# tinyg_g2_breakout_v1.net
KiCad netlist of a schematic drawn in EAGLE
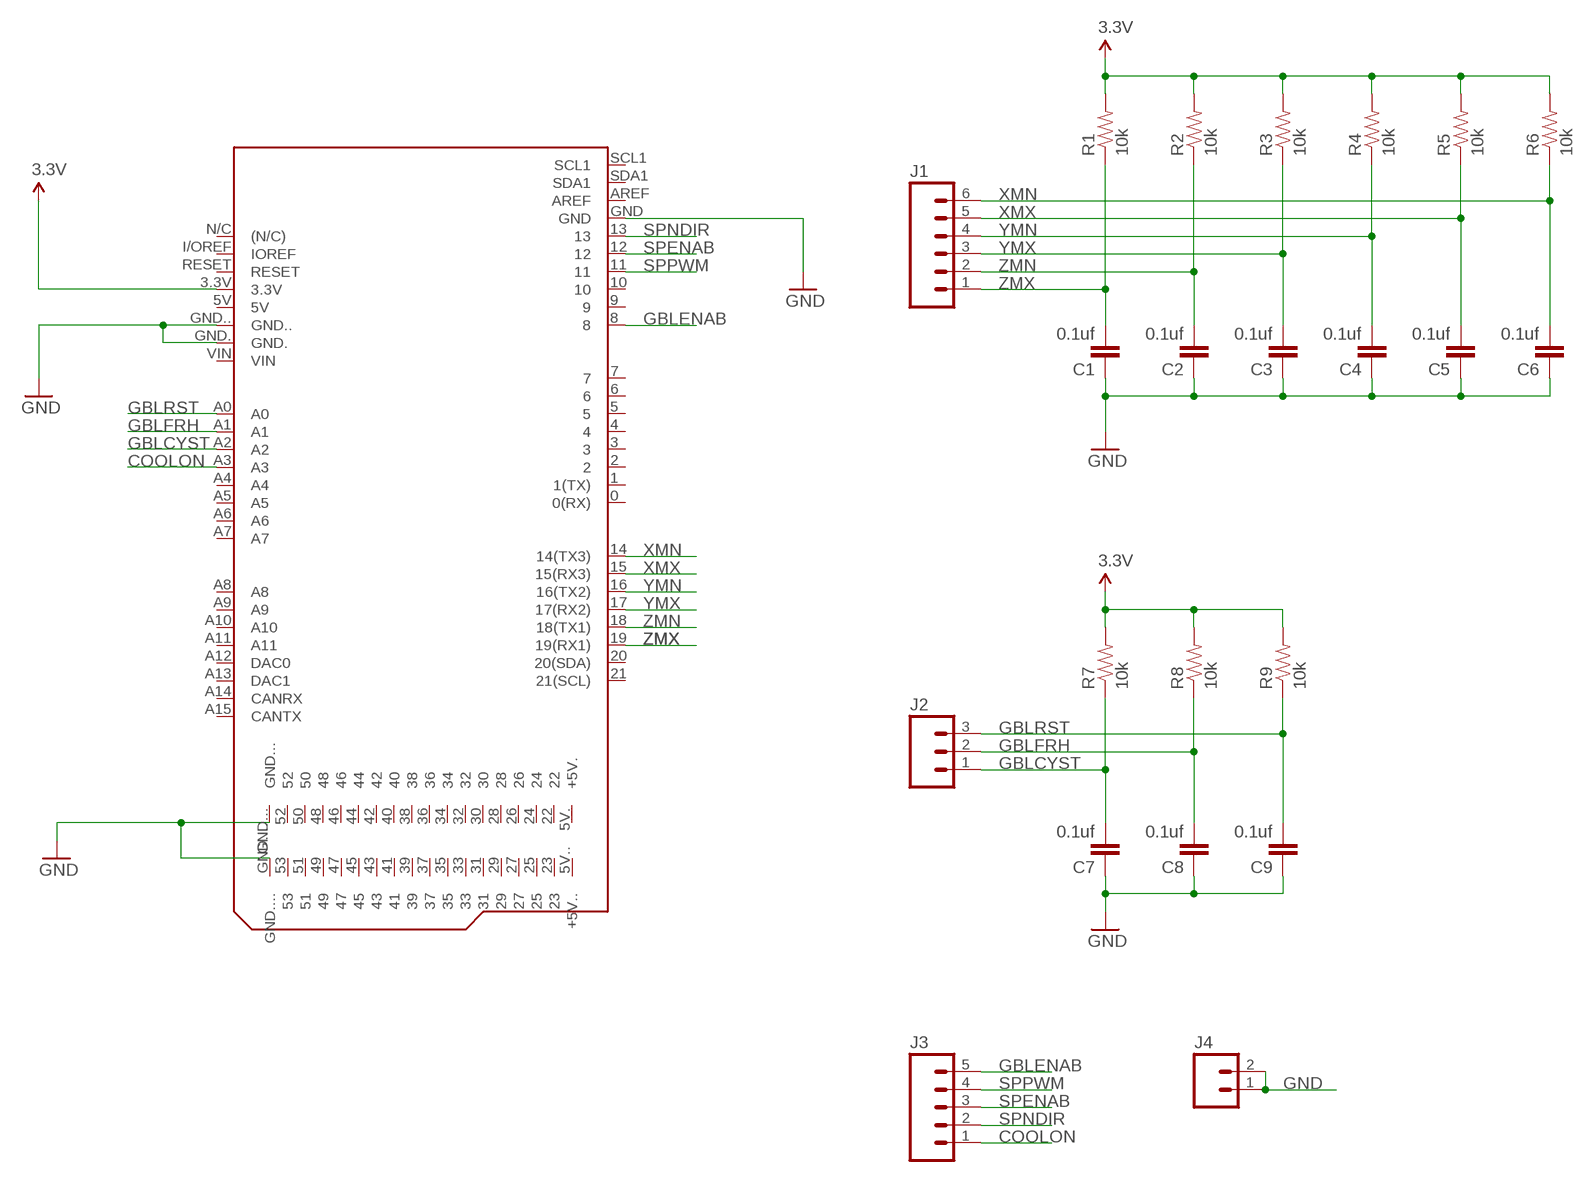
[diagram p0: schematic, sheet 1]

(export (version "E")
  (design (tool "Eeschema 10.0.6"))
  (components
    (comp (ref "C1")
      (value "0.1uf")
      (footprint "eagle-import:CAP-PTH-SMALL")
      (libsource (lib "eagle-import") (part "CAPPTH"))
    )
    (comp (ref "C2")
      (value "0.1uf")
      (footprint "eagle-import:CAP-PTH-SMALL")
      (libsource (lib "eagle-import") (part "CAPPTH"))
    )
    (comp (ref "C3")
      (value "0.1uf")
      (footprint "eagle-import:CAP-PTH-SMALL")
      (libsource (lib "eagle-import") (part "CAPPTH"))
    )
    (comp (ref "C4")
      (value "0.1uf")
      (footprint "eagle-import:CAP-PTH-SMALL")
      (libsource (lib "eagle-import") (part "CAPPTH"))
    )
    (comp (ref "C5")
      (value "0.1uf")
      (footprint "eagle-import:CAP-PTH-SMALL")
      (libsource (lib "eagle-import") (part "CAPPTH"))
    )
    (comp (ref "C6")
      (value "0.1uf")
      (footprint "eagle-import:CAP-PTH-SMALL")
      (libsource (lib "eagle-import") (part "CAPPTH"))
    )
    (comp (ref "C7")
      (value "0.1uf")
      (footprint "eagle-import:CAP-PTH-SMALL")
      (libsource (lib "eagle-import") (part "CAPPTH"))
    )
    (comp (ref "C8")
      (value "0.1uf")
      (footprint "eagle-import:CAP-PTH-SMALL")
      (libsource (lib "eagle-import") (part "CAPPTH"))
    )
    (comp (ref "C9")
      (value "0.1uf")
      (footprint "eagle-import:CAP-PTH-SMALL")
      (libsource (lib "eagle-import") (part "CAPPTH"))
    )
    (comp (ref "J1")
      (value "M06SILK_FEMALE_PTH")
      (footprint "eagle-import:1X06")
      (libsource (lib "eagle-import") (part "M06SILK_FEMALE_PTH"))
    )
    (comp (ref "J2")
      (value "M03PTH")
      (footprint "eagle-import:1X03")
      (libsource (lib "eagle-import") (part "M03PTH"))
    )
    (comp (ref "J3")
      (value "M05PTH")
      (footprint "eagle-import:1X05")
      (libsource (lib "eagle-import") (part "M05PTH"))
    )
    (comp (ref "J4")
      (value "M02PTH")
      (footprint "eagle-import:1X02")
      (libsource (lib "eagle-import") (part "M02PTH"))
    )
    (comp (ref "PCB1")
      (value "ARDUINO_DUE_SHIELD")
      (footprint "eagle-import:ARDUINO_DUE_SHIELD")
      (libsource (lib "eagle-import") (part "ARDUINO_DUE_SHIELD"))
    )
    (comp (ref "R1")
      (value "10k")
      (footprint "eagle-import:AXIAL-0.3")
      (libsource (lib "eagle-import") (part "RESISTORAXIAL-0.3"))
    )
    (comp (ref "R2")
      (value "10k")
      (footprint "eagle-import:AXIAL-0.3")
      (libsource (lib "eagle-import") (part "RESISTORAXIAL-0.3"))
    )
    (comp (ref "R3")
      (value "10k")
      (footprint "eagle-import:AXIAL-0.3")
      (libsource (lib "eagle-import") (part "RESISTORAXIAL-0.3"))
    )
    (comp (ref "R4")
      (value "10k")
      (footprint "eagle-import:AXIAL-0.3")
      (libsource (lib "eagle-import") (part "RESISTORAXIAL-0.3"))
    )
    (comp (ref "R5")
      (value "10k")
      (footprint "eagle-import:AXIAL-0.3")
      (libsource (lib "eagle-import") (part "RESISTORAXIAL-0.3"))
    )
    (comp (ref "R6")
      (value "10k")
      (footprint "eagle-import:AXIAL-0.3")
      (libsource (lib "eagle-import") (part "RESISTORAXIAL-0.3"))
    )
    (comp (ref "R7")
      (value "10k")
      (footprint "eagle-import:AXIAL-0.3")
      (libsource (lib "eagle-import") (part "RESISTORAXIAL-0.3"))
    )
    (comp (ref "R8")
      (value "10k")
      (footprint "eagle-import:AXIAL-0.3")
      (libsource (lib "eagle-import") (part "RESISTORAXIAL-0.3"))
    )
    (comp (ref "R9")
      (value "10k")
      (footprint "eagle-import:AXIAL-0.3")
      (libsource (lib "eagle-import") (part "RESISTORAXIAL-0.3"))
    )
  )
  (nets
    (net (code "1") (name "/COOLON") (class "Default")
      (node (ref "J3") (pin "1") (pinfunction "1_1") (pintype "passive"))
      (node (ref "PCB1") (pin "A3") (pinfunction "A3_A3") (pintype "bidirectional"))
    )
    (net (code "2") (name "/GBLCYST") (class "Default")
      (node (ref "C7") (pin "2") (pinfunction "2_2") (pintype "passive"))
      (node (ref "J2") (pin "1") (pinfunction "1_1") (pintype "passive"))
      (node (ref "PCB1") (pin "A2") (pinfunction "A2_A2") (pintype "bidirectional"))
      (node (ref "R7") (pin "P$1") (pinfunction "1_P$1") (pintype "passive"))
    )
    (net (code "3") (name "/GBLENAB") (class "Default")
      (node (ref "J3") (pin "5") (pinfunction "5_5") (pintype "passive"))
      (node (ref "PCB1") (pin "8") (pinfunction "8_8") (pintype "bidirectional"))
    )
    (net (code "4") (name "/GBLFRH") (class "Default")
      (node (ref "C8") (pin "2") (pinfunction "2_2") (pintype "passive"))
      (node (ref "J2") (pin "2") (pinfunction "2_2") (pintype "passive"))
      (node (ref "PCB1") (pin "A1") (pinfunction "A1_A1") (pintype "bidirectional"))
      (node (ref "R8") (pin "P$1") (pinfunction "1_P$1") (pintype "passive"))
    )
    (net (code "5") (name "/GBLRST") (class "Default")
      (node (ref "C9") (pin "2") (pinfunction "2_2") (pintype "passive"))
      (node (ref "J2") (pin "3") (pinfunction "3_3") (pintype "passive"))
      (node (ref "PCB1") (pin "A0") (pinfunction "A0_A0") (pintype "bidirectional"))
      (node (ref "R9") (pin "P$1") (pinfunction "1_P$1") (pintype "passive"))
    )
    (net (code "6") (name "/SPENAB") (class "Default")
      (node (ref "J3") (pin "3") (pinfunction "3_3") (pintype "passive"))
      (node (ref "PCB1") (pin "12") (pinfunction "12_12") (pintype "bidirectional"))
    )
    (net (code "7") (name "/SPNDIR") (class "Default")
      (node (ref "J3") (pin "2") (pinfunction "2_2") (pintype "passive"))
      (node (ref "PCB1") (pin "13") (pinfunction "13_13") (pintype "bidirectional"))
    )
    (net (code "8") (name "/SPPWM") (class "Default")
      (node (ref "J3") (pin "4") (pinfunction "4_4") (pintype "passive"))
      (node (ref "PCB1") (pin "11") (pinfunction "11_11") (pintype "bidirectional"))
    )
    (net (code "9") (name "/XMN") (class "Default")
      (node (ref "C6") (pin "2") (pinfunction "2_2") (pintype "passive"))
      (node (ref "J1") (pin "6") (pinfunction "6_6") (pintype "passive"))
      (node (ref "PCB1") (pin "14") (pinfunction "14(TX3)_14") (pintype "bidirectional"))
      (node (ref "R6") (pin "P$1") (pinfunction "1_P$1") (pintype "passive"))
    )
    (net (code "10") (name "/XMX") (class "Default")
      (node (ref "C5") (pin "2") (pinfunction "2_2") (pintype "passive"))
      (node (ref "J1") (pin "5") (pinfunction "5_5") (pintype "passive"))
      (node (ref "PCB1") (pin "15") (pinfunction "15(RX3)_15") (pintype "bidirectional"))
      (node (ref "R5") (pin "P$1") (pinfunction "1_P$1") (pintype "passive"))
    )
    (net (code "11") (name "/YMN") (class "Default")
      (node (ref "C4") (pin "2") (pinfunction "2_2") (pintype "passive"))
      (node (ref "J1") (pin "4") (pinfunction "4_4") (pintype "passive"))
      (node (ref "PCB1") (pin "16") (pinfunction "16(TX2)_16") (pintype "bidirectional"))
      (node (ref "R4") (pin "P$1") (pinfunction "1_P$1") (pintype "passive"))
    )
    (net (code "12") (name "/YMX") (class "Default")
      (node (ref "C3") (pin "2") (pinfunction "2_2") (pintype "passive"))
      (node (ref "J1") (pin "3") (pinfunction "3_3") (pintype "passive"))
      (node (ref "PCB1") (pin "17") (pinfunction "17(RX2)_17") (pintype "bidirectional"))
      (node (ref "R3") (pin "P$1") (pinfunction "1_P$1") (pintype "passive"))
    )
    (net (code "13") (name "/ZMN") (class "Default")
      (node (ref "C2") (pin "2") (pinfunction "2_2") (pintype "passive"))
      (node (ref "J1") (pin "2") (pinfunction "2_2") (pintype "passive"))
      (node (ref "PCB1") (pin "18") (pinfunction "18(TX1)_18") (pintype "bidirectional"))
      (node (ref "R2") (pin "P$1") (pinfunction "1_P$1") (pintype "passive"))
    )
    (net (code "14") (name "/ZMX") (class "Default")
      (node (ref "C1") (pin "2") (pinfunction "2_2") (pintype "passive"))
      (node (ref "J1") (pin "1") (pinfunction "1_1") (pintype "passive"))
      (node (ref "PCB1") (pin "19") (pinfunction "19(RX1)_19") (pintype "bidirectional"))
      (node (ref "R1") (pin "P$1") (pinfunction "1_P$1") (pintype "passive"))
    )
    (net (code "15") (name "3.3V") (class "Default")
      (node (ref "PCB1") (pin "3.3V") (pinfunction "3.3V_3.3V") (pintype "bidirectional"))
      (node (ref "R1") (pin "P$2") (pinfunction "2_P$2") (pintype "passive"))
      (node (ref "R2") (pin "P$2") (pinfunction "2_P$2") (pintype "passive"))
      (node (ref "R3") (pin "P$2") (pinfunction "2_P$2") (pintype "passive"))
      (node (ref "R4") (pin "P$2") (pinfunction "2_P$2") (pintype "passive"))
      (node (ref "R5") (pin "P$2") (pinfunction "2_P$2") (pintype "passive"))
      (node (ref "R6") (pin "P$2") (pinfunction "2_P$2") (pintype "passive"))
      (node (ref "R7") (pin "P$2") (pinfunction "2_P$2") (pintype "passive"))
      (node (ref "R8") (pin "P$2") (pinfunction "2_P$2") (pintype "passive"))
      (node (ref "R9") (pin "P$2") (pinfunction "2_P$2") (pintype "passive"))
    )
    (net (code "16") (name "GND") (class "Default")
      (node (ref "C1") (pin "1") (pinfunction "1_1") (pintype "passive"))
      (node (ref "C2") (pin "1") (pinfunction "1_1") (pintype "passive"))
      (node (ref "C3") (pin "1") (pinfunction "1_1") (pintype "passive"))
      (node (ref "C4") (pin "1") (pinfunction "1_1") (pintype "passive"))
      (node (ref "C5") (pin "1") (pinfunction "1_1") (pintype "passive"))
      (node (ref "C6") (pin "1") (pinfunction "1_1") (pintype "passive"))
      (node (ref "C7") (pin "1") (pinfunction "1_1") (pintype "passive"))
      (node (ref "C8") (pin "1") (pinfunction "1_1") (pintype "passive"))
      (node (ref "C9") (pin "1") (pinfunction "1_1") (pintype "passive"))
      (node (ref "J4") (pin "1") (pinfunction "1_1") (pintype "passive"))
      (node (ref "J4") (pin "2") (pinfunction "2_2") (pintype "passive"))
      (node (ref "PCB1") (pin "GND") (pinfunction "GND_GND") (pintype "bidirectional"))
      (node (ref "PCB1") (pin "GND.") (pinfunction "GND._GND.") (pintype "bidirectional"))
      (node (ref "PCB1") (pin "GND..") (pinfunction "GND.._GND..") (pintype "bidirectional"))
      (node (ref "PCB1") (pin "GND...") (pinfunction "GND..._GND...") (pintype "bidirectional"))
      (node (ref "PCB1") (pin "GND....") (pinfunction "GND...._GND....") (pintype "bidirectional"))
    )
    (net (code "17") (name "unconnected-(PCB1-(N{slash}C)-PadN{slash}C)") (class "Default")
      (node (ref "PCB1") (pin "N/C") (pinfunction "(N/C)_N/C") (pintype "bidirectional"))
    )
    (net (code "18") (name "unconnected-(PCB1-+5V.-Pad5V.)") (class "Default")
      (node (ref "PCB1") (pin "5V.") (pinfunction "+5V._5V.") (pintype "bidirectional"))
    )
    (net (code "19") (name "unconnected-(PCB1-+5V..-Pad5V..)") (class "Default")
      (node (ref "PCB1") (pin "5V..") (pinfunction "+5V.._5V..") (pintype "bidirectional"))
    )
    (net (code "20") (name "unconnected-(PCB1-0(RX)-Pad0)") (class "Default")
      (node (ref "PCB1") (pin "0") (pinfunction "0(RX)_0") (pintype "bidirectional"))
    )
    (net (code "21") (name "unconnected-(PCB1-1(TX)-Pad1)") (class "Default")
      (node (ref "PCB1") (pin "1") (pinfunction "1(TX)_1") (pintype "bidirectional"))
    )
    (net (code "22") (name "unconnected-(PCB1-20(SDA)-Pad20)") (class "Default")
      (node (ref "PCB1") (pin "20") (pinfunction "20(SDA)_20") (pintype "bidirectional"))
    )
    (net (code "23") (name "unconnected-(PCB1-21(SCL)-Pad21)") (class "Default")
      (node (ref "PCB1") (pin "21") (pinfunction "21(SCL)_21") (pintype "bidirectional"))
    )
    (net (code "24") (name "unconnected-(PCB1-CANRX-PadA14)") (class "Default")
      (node (ref "PCB1") (pin "A14") (pinfunction "CANRX_A14") (pintype "bidirectional"))
    )
    (net (code "25") (name "unconnected-(PCB1-CANTX-PadA15)") (class "Default")
      (node (ref "PCB1") (pin "A15") (pinfunction "CANTX_A15") (pintype "bidirectional"))
    )
    (net (code "26") (name "unconnected-(PCB1-DAC0-PadA12)") (class "Default")
      (node (ref "PCB1") (pin "A12") (pinfunction "DAC0_A12") (pintype "bidirectional"))
    )
    (net (code "27") (name "unconnected-(PCB1-DAC1-PadA13)") (class "Default")
      (node (ref "PCB1") (pin "A13") (pinfunction "DAC1_A13") (pintype "bidirectional"))
    )
    (net (code "28") (name "unconnected-(PCB1-IOREF-PadI{slash}OREF)") (class "Default")
      (node (ref "PCB1") (pin "I/OREF") (pinfunction "IOREF_I/OREF") (pintype "bidirectional"))
    )
    (net (code "29") (name "unconnected-(PCB1-Pad2)") (class "Default")
      (node (ref "PCB1") (pin "2") (pinfunction "2_2") (pintype "bidirectional"))
    )
    (net (code "30") (name "unconnected-(PCB1-Pad3)") (class "Default")
      (node (ref "PCB1") (pin "3") (pinfunction "3_3") (pintype "bidirectional"))
    )
    (net (code "31") (name "unconnected-(PCB1-Pad4)") (class "Default")
      (node (ref "PCB1") (pin "4") (pinfunction "4_4") (pintype "bidirectional"))
    )
    (net (code "32") (name "unconnected-(PCB1-Pad5)") (class "Default")
      (node (ref "PCB1") (pin "5") (pinfunction "5_5") (pintype "bidirectional"))
    )
    (net (code "33") (name "unconnected-(PCB1-Pad5V)") (class "Default")
      (node (ref "PCB1") (pin "5V") (pinfunction "5V_5V") (pintype "bidirectional"))
    )
    (net (code "34") (name "unconnected-(PCB1-Pad6)") (class "Default")
      (node (ref "PCB1") (pin "6") (pinfunction "6_6") (pintype "bidirectional"))
    )
    (net (code "35") (name "unconnected-(PCB1-Pad7)") (class "Default")
      (node (ref "PCB1") (pin "7") (pinfunction "7_7") (pintype "bidirectional"))
    )
    (net (code "36") (name "unconnected-(PCB1-Pad9)") (class "Default")
      (node (ref "PCB1") (pin "9") (pinfunction "9_9") (pintype "bidirectional"))
    )
    (net (code "37") (name "unconnected-(PCB1-Pad10)") (class "Default")
      (node (ref "PCB1") (pin "10") (pinfunction "10_10") (pintype "bidirectional"))
    )
    (net (code "38") (name "unconnected-(PCB1-Pad22)") (class "Default")
      (node (ref "PCB1") (pin "22") (pinfunction "22_22") (pintype "bidirectional"))
    )
    (net (code "39") (name "unconnected-(PCB1-Pad23)") (class "Default")
      (node (ref "PCB1") (pin "23") (pinfunction "23_23") (pintype "bidirectional"))
    )
    (net (code "40") (name "unconnected-(PCB1-Pad24)") (class "Default")
      (node (ref "PCB1") (pin "24") (pinfunction "24_24") (pintype "bidirectional"))
    )
    (net (code "41") (name "unconnected-(PCB1-Pad25)") (class "Default")
      (node (ref "PCB1") (pin "25") (pinfunction "25_25") (pintype "bidirectional"))
    )
    (net (code "42") (name "unconnected-(PCB1-Pad26)") (class "Default")
      (node (ref "PCB1") (pin "26") (pinfunction "26_26") (pintype "bidirectional"))
    )
    (net (code "43") (name "unconnected-(PCB1-Pad27)") (class "Default")
      (node (ref "PCB1") (pin "27") (pinfunction "27_27") (pintype "bidirectional"))
    )
    (net (code "44") (name "unconnected-(PCB1-Pad28)") (class "Default")
      (node (ref "PCB1") (pin "28") (pinfunction "28_28") (pintype "bidirectional"))
    )
    (net (code "45") (name "unconnected-(PCB1-Pad29)") (class "Default")
      (node (ref "PCB1") (pin "29") (pinfunction "29_29") (pintype "bidirectional"))
    )
    (net (code "46") (name "unconnected-(PCB1-Pad30)") (class "Default")
      (node (ref "PCB1") (pin "30") (pinfunction "30_30") (pintype "bidirectional"))
    )
    (net (code "47") (name "unconnected-(PCB1-Pad31)") (class "Default")
      (node (ref "PCB1") (pin "31") (pinfunction "31_31") (pintype "bidirectional"))
    )
    (net (code "48") (name "unconnected-(PCB1-Pad32)") (class "Default")
      (node (ref "PCB1") (pin "32") (pinfunction "32_32") (pintype "bidirectional"))
    )
    (net (code "49") (name "unconnected-(PCB1-Pad33)") (class "Default")
      (node (ref "PCB1") (pin "33") (pinfunction "33_33") (pintype "bidirectional"))
    )
    (net (code "50") (name "unconnected-(PCB1-Pad34)") (class "Default")
      (node (ref "PCB1") (pin "34") (pinfunction "34_34") (pintype "bidirectional"))
    )
    (net (code "51") (name "unconnected-(PCB1-Pad35)") (class "Default")
      (node (ref "PCB1") (pin "35") (pinfunction "35_35") (pintype "bidirectional"))
    )
    (net (code "52") (name "unconnected-(PCB1-Pad36)") (class "Default")
      (node (ref "PCB1") (pin "36") (pinfunction "36_36") (pintype "bidirectional"))
    )
    (net (code "53") (name "unconnected-(PCB1-Pad37)") (class "Default")
      (node (ref "PCB1") (pin "37") (pinfunction "37_37") (pintype "bidirectional"))
    )
    (net (code "54") (name "unconnected-(PCB1-Pad38)") (class "Default")
      (node (ref "PCB1") (pin "38") (pinfunction "38_38") (pintype "bidirectional"))
    )
    (net (code "55") (name "unconnected-(PCB1-Pad39)") (class "Default")
      (node (ref "PCB1") (pin "39") (pinfunction "39_39") (pintype "bidirectional"))
    )
    (net (code "56") (name "unconnected-(PCB1-Pad40)") (class "Default")
      (node (ref "PCB1") (pin "40") (pinfunction "40_40") (pintype "bidirectional"))
    )
    (net (code "57") (name "unconnected-(PCB1-Pad41)") (class "Default")
      (node (ref "PCB1") (pin "41") (pinfunction "41_41") (pintype "bidirectional"))
    )
    (net (code "58") (name "unconnected-(PCB1-Pad42)") (class "Default")
      (node (ref "PCB1") (pin "42") (pinfunction "42_42") (pintype "bidirectional"))
    )
    (net (code "59") (name "unconnected-(PCB1-Pad43)") (class "Default")
      (node (ref "PCB1") (pin "43") (pinfunction "43_43") (pintype "bidirectional"))
    )
    (net (code "60") (name "unconnected-(PCB1-Pad44)") (class "Default")
      (node (ref "PCB1") (pin "44") (pinfunction "44_44") (pintype "bidirectional"))
    )
    (net (code "61") (name "unconnected-(PCB1-Pad45)") (class "Default")
      (node (ref "PCB1") (pin "45") (pinfunction "45_45") (pintype "bidirectional"))
    )
    (net (code "62") (name "unconnected-(PCB1-Pad46)") (class "Default")
      (node (ref "PCB1") (pin "46") (pinfunction "46_46") (pintype "bidirectional"))
    )
    (net (code "63") (name "unconnected-(PCB1-Pad47)") (class "Default")
      (node (ref "PCB1") (pin "47") (pinfunction "47_47") (pintype "bidirectional"))
    )
    (net (code "64") (name "unconnected-(PCB1-Pad48)") (class "Default")
      (node (ref "PCB1") (pin "48") (pinfunction "48_48") (pintype "bidirectional"))
    )
    (net (code "65") (name "unconnected-(PCB1-Pad49)") (class "Default")
      (node (ref "PCB1") (pin "49") (pinfunction "49_49") (pintype "bidirectional"))
    )
    (net (code "66") (name "unconnected-(PCB1-Pad50)") (class "Default")
      (node (ref "PCB1") (pin "50") (pinfunction "50_50") (pintype "bidirectional"))
    )
    (net (code "67") (name "unconnected-(PCB1-Pad51)") (class "Default")
      (node (ref "PCB1") (pin "51") (pinfunction "51_51") (pintype "bidirectional"))
    )
    (net (code "68") (name "unconnected-(PCB1-Pad52)") (class "Default")
      (node (ref "PCB1") (pin "52") (pinfunction "52_52") (pintype "bidirectional"))
    )
    (net (code "69") (name "unconnected-(PCB1-Pad53)") (class "Default")
      (node (ref "PCB1") (pin "53") (pinfunction "53_53") (pintype "bidirectional"))
    )
    (net (code "70") (name "unconnected-(PCB1-PadA4)") (class "Default")
      (node (ref "PCB1") (pin "A4") (pinfunction "A4_A4") (pintype "bidirectional"))
    )
    (net (code "71") (name "unconnected-(PCB1-PadA5)") (class "Default")
      (node (ref "PCB1") (pin "A5") (pinfunction "A5_A5") (pintype "bidirectional"))
    )
    (net (code "72") (name "unconnected-(PCB1-PadA6)") (class "Default")
      (node (ref "PCB1") (pin "A6") (pinfunction "A6_A6") (pintype "bidirectional"))
    )
    (net (code "73") (name "unconnected-(PCB1-PadA7)") (class "Default")
      (node (ref "PCB1") (pin "A7") (pinfunction "A7_A7") (pintype "bidirectional"))
    )
    (net (code "74") (name "unconnected-(PCB1-PadA8)") (class "Default")
      (node (ref "PCB1") (pin "A8") (pinfunction "A8_A8") (pintype "bidirectional"))
    )
    (net (code "75") (name "unconnected-(PCB1-PadA9)") (class "Default")
      (node (ref "PCB1") (pin "A9") (pinfunction "A9_A9") (pintype "bidirectional"))
    )
    (net (code "76") (name "unconnected-(PCB1-PadA10)") (class "Default")
      (node (ref "PCB1") (pin "A10") (pinfunction "A10_A10") (pintype "bidirectional"))
    )
    (net (code "77") (name "unconnected-(PCB1-PadA11)") (class "Default")
      (node (ref "PCB1") (pin "A11") (pinfunction "A11_A11") (pintype "bidirectional"))
    )
    (net (code "78") (name "unconnected-(PCB1-PadAREF)") (class "Default")
      (node (ref "PCB1") (pin "AREF") (pinfunction "AREF_AREF") (pintype "bidirectional"))
    )
    (net (code "79") (name "unconnected-(PCB1-PadRESET)") (class "Default")
      (node (ref "PCB1") (pin "RESET") (pinfunction "RESET_RESET") (pintype "bidirectional"))
    )
    (net (code "80") (name "unconnected-(PCB1-PadSCL1)") (class "Default")
      (node (ref "PCB1") (pin "SCL1") (pinfunction "SCL1_SCL1") (pintype "bidirectional"))
    )
    (net (code "81") (name "unconnected-(PCB1-PadSDA1)") (class "Default")
      (node (ref "PCB1") (pin "SDA1") (pinfunction "SDA1_SDA1") (pintype "bidirectional"))
    )
    (net (code "82") (name "unconnected-(PCB1-PadVIN)") (class "Default")
      (node (ref "PCB1") (pin "VIN") (pinfunction "VIN_VIN") (pintype "bidirectional"))
    )
  )
)
